# Camera.net
KiCad netlist of a schematic drawn in Altium Designer
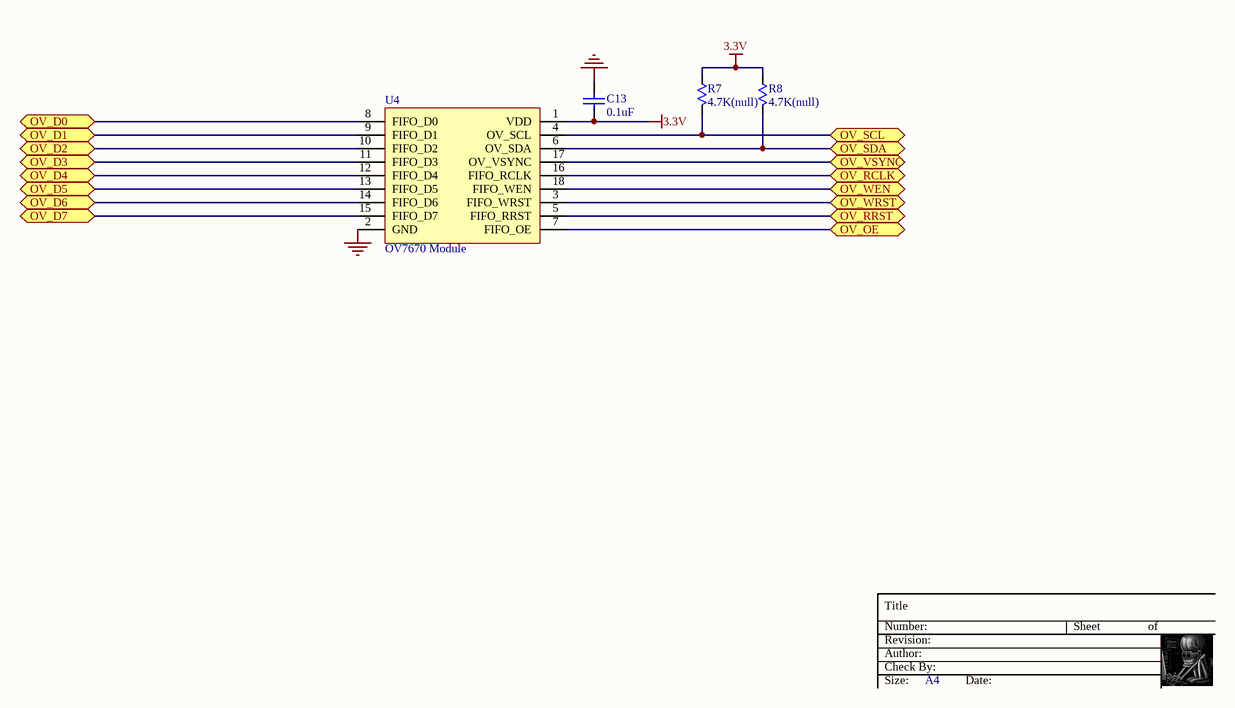
[diagram p0: Camera.SchDoc]

(export (version "E")
  (design (tool "Eeschema 10.0.6"))
  (components
    (comp (ref "C13")
      (value "0.1uF")
      (footprint "C0603-S")
      (description "Capacitor")
      (libsource (lib "Passive Components Class") (part "CAP"))
    )
    (comp (ref "R7")
      (value "4.7K(null)")
      (footprint "R0603-S")
      (description "Resistor")
      (libsource (lib "Passive Components Class") (part "RES"))
    )
    (comp (ref "R8")
      (value "4.7K(null)")
      (footprint "R0603-S")
      (description "Resistor")
      (libsource (lib "Passive Components Class") (part "RES"))
    )
    (comp (ref "U4")
      (value "OV7670 Module")
      (footprint "OV7670_MOD")
      (description "ALIENTEK OV7670 Module")
      (libsource (lib "FX Class") (part "OV7670_MOD"))
    )
  )
  (nets
    (net (code "1") (name "/OV_D0") (class "Default")
      (node (ref "U4") (pin "8") (pinfunction "FIFO_D0_8") (pintype "passive"))
    )
    (net (code "2") (name "/OV_D1") (class "Default")
      (node (ref "U4") (pin "9") (pinfunction "FIFO_D1_9") (pintype "passive"))
    )
    (net (code "3") (name "/OV_D2") (class "Default")
      (node (ref "U4") (pin "10") (pinfunction "FIFO_D2_10") (pintype "passive"))
    )
    (net (code "4") (name "/OV_D3") (class "Default")
      (node (ref "U4") (pin "11") (pinfunction "FIFO_D3_11") (pintype "passive"))
    )
    (net (code "5") (name "/OV_D4") (class "Default")
      (node (ref "U4") (pin "12") (pinfunction "FIFO_D4_12") (pintype "passive"))
    )
    (net (code "6") (name "/OV_D5") (class "Default")
      (node (ref "U4") (pin "13") (pinfunction "FIFO_D5_13") (pintype "passive"))
    )
    (net (code "7") (name "/OV_D6") (class "Default")
      (node (ref "U4") (pin "14") (pinfunction "FIFO_D6_14") (pintype "passive"))
    )
    (net (code "8") (name "/OV_D7") (class "Default")
      (node (ref "U4") (pin "15") (pinfunction "FIFO_D7_15") (pintype "passive"))
    )
    (net (code "9") (name "/OV_OE") (class "Default")
      (node (ref "U4") (pin "7") (pinfunction "FIFO_OE_7") (pintype "passive"))
    )
    (net (code "10") (name "/OV_RCLK") (class "Default")
      (node (ref "U4") (pin "16") (pinfunction "FIFO_RCLK_16") (pintype "passive"))
    )
    (net (code "11") (name "/OV_RRST") (class "Default")
      (node (ref "U4") (pin "5") (pinfunction "FIFO_RRST_5") (pintype "passive"))
    )
    (net (code "12") (name "/OV_SCL") (class "Default")
      (node (ref "R7") (pin "1") (pinfunction "1_1") (pintype "passive"))
      (node (ref "U4") (pin "4") (pinfunction "OV_SCL_4") (pintype "passive"))
    )
    (net (code "13") (name "/OV_SDA") (class "Default")
      (node (ref "R8") (pin "1") (pinfunction "1_1") (pintype "passive"))
      (node (ref "U4") (pin "6") (pinfunction "OV_SDA_6") (pintype "passive"))
    )
    (net (code "14") (name "/OV_VSYNC") (class "Default")
      (node (ref "U4") (pin "17") (pinfunction "OV_VSYNC_17") (pintype "passive"))
    )
    (net (code "15") (name "/OV_WEN") (class "Default")
      (node (ref "U4") (pin "18") (pinfunction "FIFO_WEN_18") (pintype "passive"))
    )
    (net (code "16") (name "/OV_WRST") (class "Default")
      (node (ref "U4") (pin "3") (pinfunction "FIFO_WRST_3") (pintype "passive"))
    )
    (net (code "17") (name "3.3V") (class "Default")
      (node (ref "C13") (pin "1") (pinfunction "1_1") (pintype "passive"))
      (node (ref "R7") (pin "2") (pinfunction "2_2") (pintype "passive"))
      (node (ref "R8") (pin "2") (pinfunction "2_2") (pintype "passive"))
      (node (ref "U4") (pin "1") (pinfunction "VDD_1") (pintype "passive"))
    )
    (net (code "18") (name "GND") (class "Default")
      (node (ref "C13") (pin "2") (pinfunction "2_2") (pintype "passive"))
      (node (ref "U4") (pin "2") (pinfunction "GND_2") (pintype "passive"))
    )
  )
)
